# C64_PS.net
KiCad netlist of a schematic drawn in EAGLE
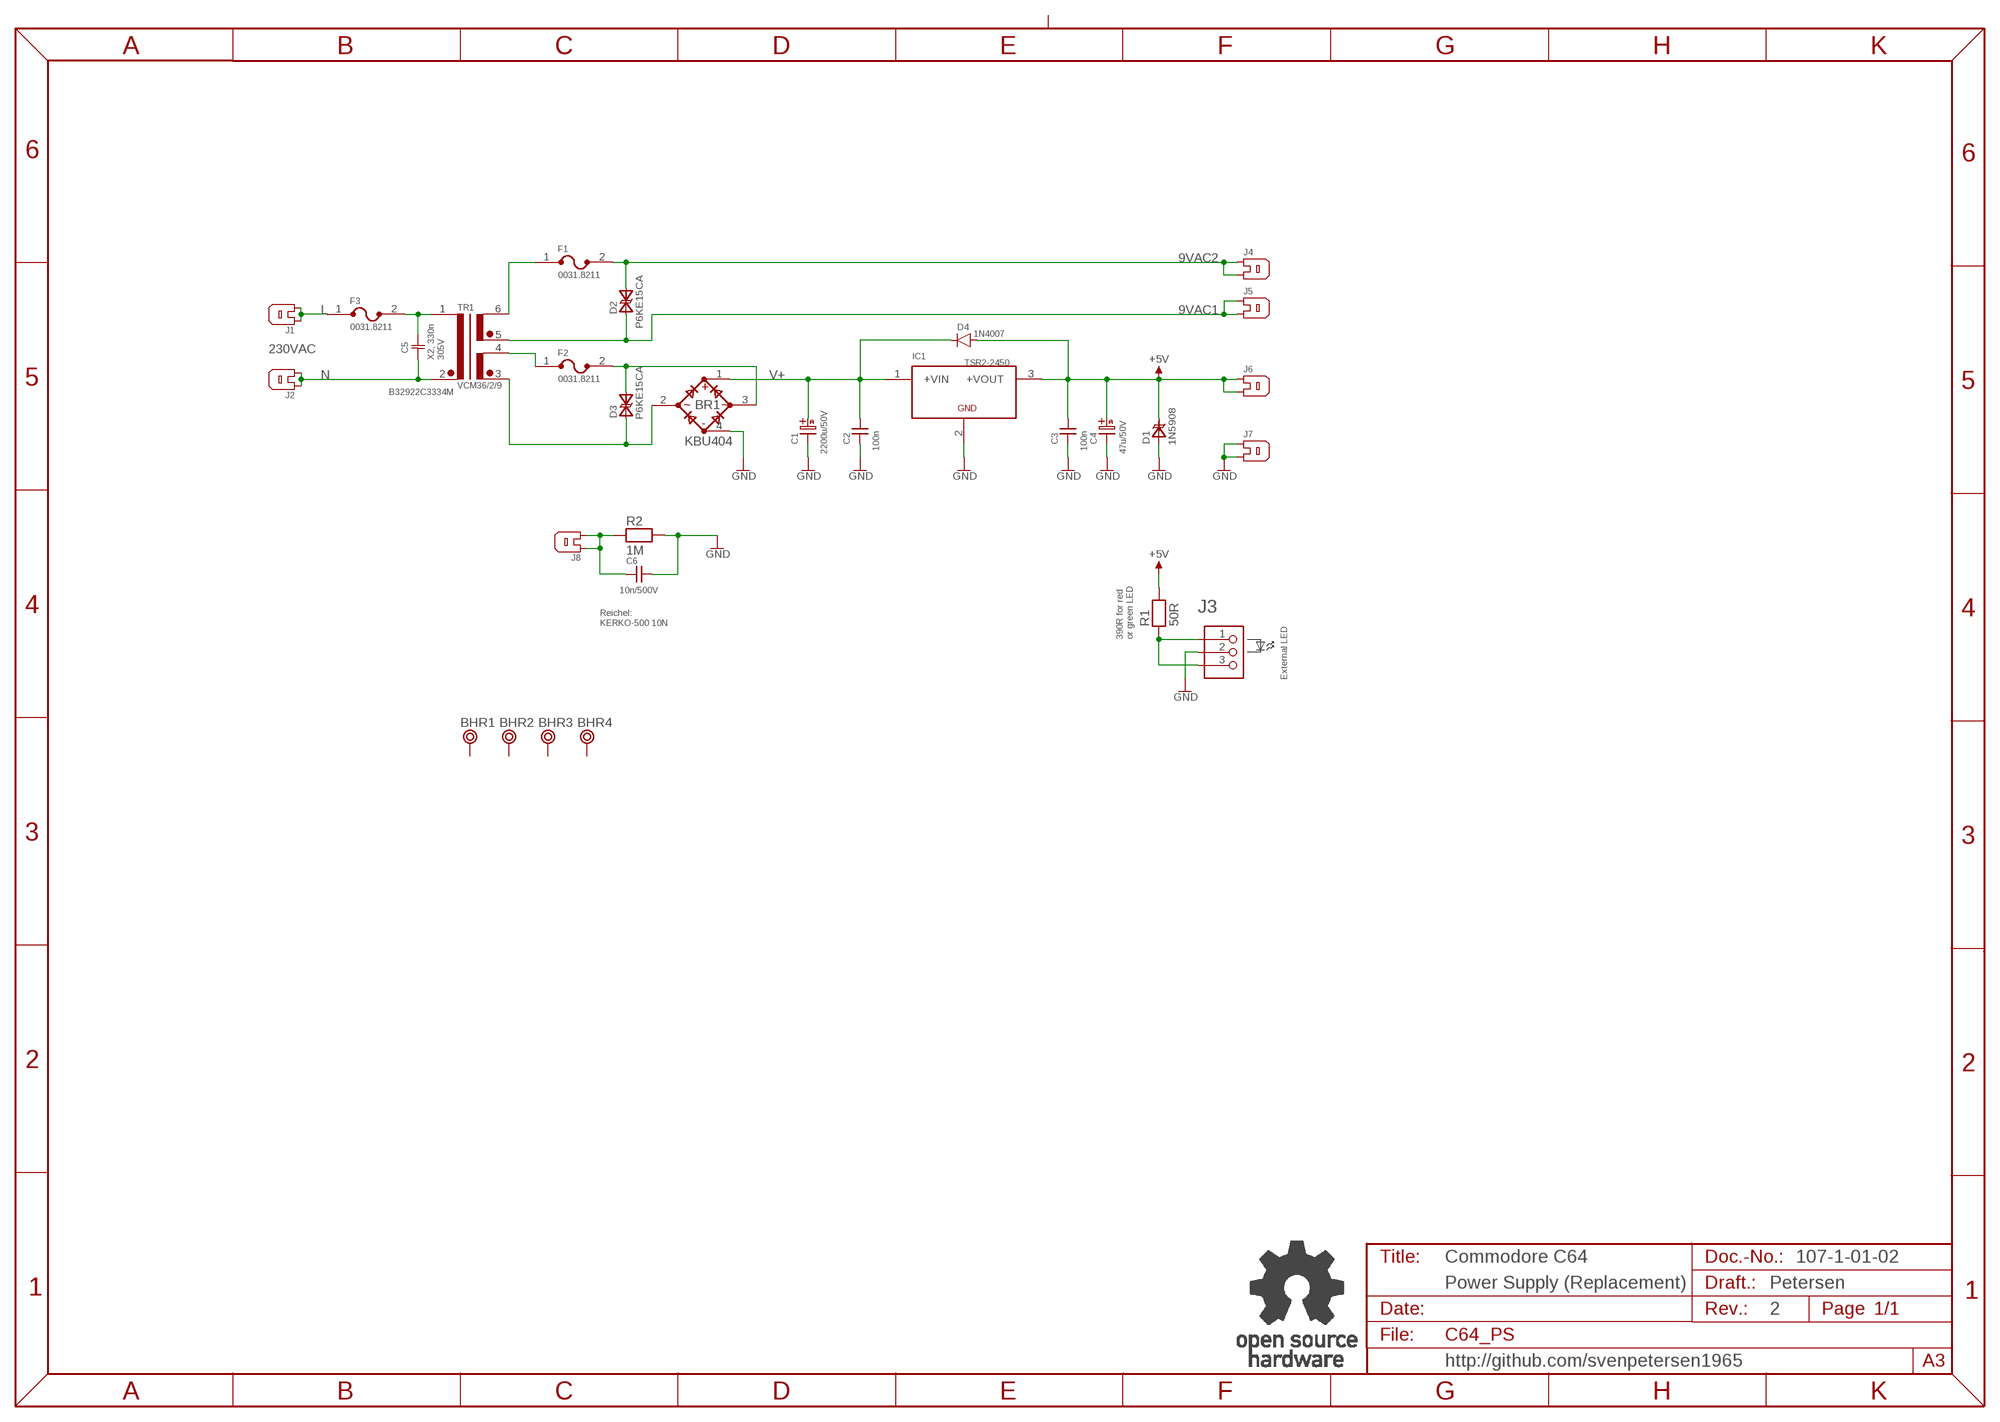
[diagram p0: schematic, sheet 1]

(export (version "E")
  (design (tool "Eeschema 10.0.6"))
  (components
    (comp (ref "BHR1")
      (value "BOHR3,3")
      (footprint "eagle-import:BOHR3,3")
      (libsource (lib "eagle-import") (part "BOHR3,3"))
    )
    (comp (ref "BHR2")
      (value "BOHR3,3")
      (footprint "eagle-import:BOHR3,3")
      (libsource (lib "eagle-import") (part "BOHR3,3"))
    )
    (comp (ref "BHR3")
      (value "BOHR3,3")
      (footprint "eagle-import:BOHR3,3")
      (libsource (lib "eagle-import") (part "BOHR3,3"))
    )
    (comp (ref "BHR4")
      (value "BOHR3,3")
      (footprint "eagle-import:BOHR3,3")
      (libsource (lib "eagle-import") (part "BOHR3,3"))
    )
    (comp (ref "BR1")
      (value "KBU404")
      (footprint "eagle-import:KBU")
      (libsource (lib "eagle-import") (part "KBU404"))
    )
    (comp (ref "C1")
      (value "2200u/50V")
      (footprint "eagle-import:C18_7,5")
      (libsource (lib "eagle-import") (part "C18/7,5"))
    )
    (comp (ref "C2")
      (value "100n")
      (footprint "eagle-import:C-5")
      (libsource (lib "eagle-import") (part "CAP02"))
    )
    (comp (ref "C3")
      (value "100n")
      (footprint "eagle-import:C-5")
      (libsource (lib "eagle-import") (part "CAP02"))
    )
    (comp (ref "C4")
      (value "47u/50V")
      (footprint "eagle-import:C07_2,5")
      (libsource (lib "eagle-import") (part "C07/2,5"))
    )
    (comp (ref "C5")
      (value "B32922C3334M")
      (footprint "eagle-import:C-18X8-RM15")
      (libsource (lib "eagle-import") (part "X2--RM15-18X8"))
    )
    (comp (ref "C6")
      (value "10n/500V")
      (footprint "eagle-import:C-5")
      (libsource (lib "eagle-import") (part "CAP02"))
    )
    (comp (ref "D1")
      (value "1N5908")
      (footprint "eagle-import:CB429")
      (libsource (lib "eagle-import") (part "1N5908"))
    )
    (comp (ref "D2")
      (value "P6KE15CA")
      (footprint "eagle-import:CB417")
      (libsource (lib "eagle-import") (part "P6KE15CA"))
    )
    (comp (ref "D3")
      (value "P6KE15CA")
      (footprint "eagle-import:CB417")
      (libsource (lib "eagle-import") (part "P6KE15CA"))
    )
    (comp (ref "D4")
      (value "1N4007")
      (footprint "eagle-import:DO-41")
      (libsource (lib "eagle-import") (part "1N4007"))
    )
    (comp (ref "F1")
      (value "0031.8211")
      (footprint "eagle-import:0031.8211")
      (libsource (lib "eagle-import") (part "0031.8211"))
    )
    (comp (ref "F2")
      (value "0031.8211")
      (footprint "eagle-import:0031.8211")
      (libsource (lib "eagle-import") (part "0031.8211"))
    )
    (comp (ref "F3")
      (value "0031.8211")
      (footprint "eagle-import:0031.8211")
      (libsource (lib "eagle-import") (part "0031.8211"))
    )
    (comp (ref "IC1")
      (value "TSR2-2450")
      (footprint "eagle-import:TSR2")
      (libsource (lib "eagle-import") (part "TSR2"))
    )
    (comp (ref "J1")
      (value "FLA6,3")
      (footprint "eagle-import:FLA6,3")
      (libsource (lib "eagle-import") (part "FLA6,3"))
    )
    (comp (ref "J2")
      (value "FLA6,3")
      (footprint "eagle-import:FLA6,3")
      (libsource (lib "eagle-import") (part "FLA6,3"))
    )
    (comp (ref "J3")
      (value "PINHD-1X3")
      (footprint "eagle-import:1X03")
      (libsource (lib "eagle-import") (part "PINHD-1X3"))
    )
    (comp (ref "J4")
      (value "FLA6,3")
      (footprint "eagle-import:FLA6,3")
      (libsource (lib "eagle-import") (part "FLA6,3"))
    )
    (comp (ref "J5")
      (value "FLA6,3")
      (footprint "eagle-import:FLA6,3")
      (libsource (lib "eagle-import") (part "FLA6,3"))
    )
    (comp (ref "J6")
      (value "FLA6,3")
      (footprint "eagle-import:FLA6,3")
      (libsource (lib "eagle-import") (part "FLA6,3"))
    )
    (comp (ref "J7")
      (value "FLA6,3")
      (footprint "eagle-import:FLA6,3")
      (libsource (lib "eagle-import") (part "FLA6,3"))
    )
    (comp (ref "J8")
      (value "FLA6,3")
      (footprint "eagle-import:FLA6,3")
      (libsource (lib "eagle-import") (part "FLA6,3"))
    )
    (comp (ref "R1")
      (value "50R")
      (footprint "eagle-import:R-10")
      (libsource (lib "eagle-import") (part "RES04"))
    )
    (comp (ref "R2")
      (value "1M")
      (footprint "eagle-import:R-10")
      (libsource (lib "eagle-import") (part "RES04"))
    )
    (comp (ref "TR1")
      (value "VCM36/2/9")
      (footprint "eagle-import:VCM36_2_9")
      (libsource (lib "eagle-import") (part "VCM36/2/9"))
    )
    (comp (ref "U$17")
      (value "OPEN_SOURCE_HW")
      (footprint "eagle-import:OPENHW")
      (libsource (lib "eagle-import") (part "OPEN_SOURCE_HW"))
    )
  )
  (nets
    (net (code "1") (name "+5V") (class "Default")
      (node (ref "C3") (pin "2") (pinfunction "2_2") (pintype "passive"))
      (node (ref "C4") (pin "A") (pinfunction "+_A") (pintype "passive"))
      (node (ref "D1") (pin "K") (pinfunction "K_K") (pintype "passive"))
      (node (ref "D4") (pin "A") (pinfunction "A_A") (pintype "passive"))
      (node (ref "IC1") (pin "3") (pinfunction "+VOUT_3") (pintype "output"))
      (node (ref "J6") (pin "1") (pinfunction "1_1") (pintype "passive"))
      (node (ref "J6") (pin "2") (pinfunction "2_2") (pintype "passive"))
      (node (ref "R1") (pin "2") (pinfunction "2_2") (pintype "passive"))
    )
    (net (code "2") (name "/9VAC1") (class "Default")
      (node (ref "D2") (pin "A") (pinfunction "A1_A") (pintype "passive"))
      (node (ref "J5") (pin "1") (pinfunction "1_1") (pintype "passive"))
      (node (ref "J5") (pin "2") (pinfunction "2_2") (pintype "passive"))
      (node (ref "TR1") (pin "5") (pinfunction "SEC12_5") (pintype "passive"))
    )
    (net (code "3") (name "/9VAC2") (class "Default")
      (node (ref "D2") (pin "K") (pinfunction "A2_K") (pintype "passive"))
      (node (ref "F1") (pin "2") (pinfunction "2_2") (pintype "passive"))
      (node (ref "J4") (pin "1") (pinfunction "1_1") (pintype "passive"))
      (node (ref "J4") (pin "2") (pinfunction "2_2") (pintype "passive"))
    )
    (net (code "4") (name "/L") (class "Default")
      (node (ref "F3") (pin "1") (pinfunction "1_1") (pintype "passive"))
      (node (ref "J1") (pin "1") (pinfunction "1_1") (pintype "passive"))
      (node (ref "J1") (pin "2") (pinfunction "2_2") (pintype "passive"))
    )
    (net (code "5") (name "/N") (class "Default")
      (node (ref "C5") (pin "1") (pinfunction "1_1") (pintype "passive"))
      (node (ref "J2") (pin "1") (pinfunction "1_1") (pintype "passive"))
      (node (ref "J2") (pin "2") (pinfunction "2_2") (pintype "passive"))
      (node (ref "TR1") (pin "2") (pinfunction "PRI2_2") (pintype "passive"))
    )
    (net (code "6") (name "/V+") (class "Default")
      (node (ref "BR1") (pin "1") (pinfunction "+_1") (pintype "passive"))
      (node (ref "C1") (pin "+") (pinfunction "+_+") (pintype "passive"))
      (node (ref "C2") (pin "2") (pinfunction "2_2") (pintype "passive"))
      (node (ref "D4") (pin "K") (pinfunction "K_K") (pintype "passive"))
      (node (ref "IC1") (pin "1") (pinfunction "+VIN_1") (pintype "input"))
    )
    (net (code "7") (name "GND") (class "Default")
      (node (ref "BR1") (pin "4") (pinfunction "-_4") (pintype "passive"))
      (node (ref "C1") (pin "-") (pinfunction "-_-") (pintype "passive"))
      (node (ref "C2") (pin "1") (pinfunction "1_1") (pintype "passive"))
      (node (ref "C3") (pin "1") (pinfunction "1_1") (pintype "passive"))
      (node (ref "C4") (pin "K") (pinfunction "-_K") (pintype "passive"))
      (node (ref "C6") (pin "2") (pinfunction "2_2") (pintype "passive"))
      (node (ref "D1") (pin "A") (pinfunction "A_A") (pintype "passive"))
      (node (ref "IC1") (pin "2") (pinfunction "GND_2") (pintype "passive"))
      (node (ref "J3") (pin "2") (pinfunction "2_2") (pintype "passive"))
      (node (ref "J7") (pin "1") (pinfunction "1_1") (pintype "passive"))
      (node (ref "J7") (pin "2") (pinfunction "2_2") (pintype "passive"))
      (node (ref "R2") (pin "2") (pinfunction "2_2") (pintype "passive"))
    )
    (net (code "8") (name "Net-(BR1-AC1)") (class "Default")
      (node (ref "BR1") (pin "2") (pinfunction "AC1_2") (pintype "passive"))
      (node (ref "D3") (pin "A") (pinfunction "A1_A") (pintype "passive"))
      (node (ref "TR1") (pin "3") (pinfunction "SEC22_3") (pintype "passive"))
    )
    (net (code "9") (name "Net-(BR1-AC2)") (class "Default")
      (node (ref "BR1") (pin "3") (pinfunction "AC2_3") (pintype "passive"))
      (node (ref "D3") (pin "K") (pinfunction "A2_K") (pintype "passive"))
      (node (ref "F2") (pin "2") (pinfunction "2_2") (pintype "passive"))
    )
    (net (code "10") (name "Net-(C6-Pad1)") (class "Default")
      (node (ref "C6") (pin "1") (pinfunction "1_1") (pintype "passive"))
      (node (ref "J8") (pin "1") (pinfunction "1_1") (pintype "passive"))
      (node (ref "J8") (pin "2") (pinfunction "2_2") (pintype "passive"))
      (node (ref "R2") (pin "1") (pinfunction "1_1") (pintype "passive"))
    )
    (net (code "11") (name "Net-(J3-Pad1)") (class "Default")
      (node (ref "J3") (pin "1") (pinfunction "1_1") (pintype "passive"))
      (node (ref "J3") (pin "3") (pinfunction "3_3") (pintype "passive"))
      (node (ref "R1") (pin "1") (pinfunction "1_1") (pintype "passive"))
    )
    (net (code "12") (name "Net-(TR1-PRI1)") (class "Default")
      (node (ref "C5") (pin "2") (pinfunction "2_2") (pintype "passive"))
      (node (ref "F3") (pin "2") (pinfunction "2_2") (pintype "passive"))
      (node (ref "TR1") (pin "1") (pinfunction "PRI1_1") (pintype "passive"))
    )
    (net (code "13") (name "Net-(TR1-SEC11)") (class "Default")
      (node (ref "F1") (pin "1") (pinfunction "1_1") (pintype "passive"))
      (node (ref "TR1") (pin "6") (pinfunction "SEC11_6") (pintype "passive"))
    )
    (net (code "14") (name "Net-(TR1-SEC21)") (class "Default")
      (node (ref "F2") (pin "1") (pinfunction "1_1") (pintype "passive"))
      (node (ref "TR1") (pin "4") (pinfunction "SEC21_4") (pintype "passive"))
    )
    (net (code "15") (name "unconnected-(BHR1-PadP$1)") (class "Default")
      (node (ref "BHR1") (pin "P$1") (pinfunction "P$1_P$1") (pintype "passive"))
    )
    (net (code "16") (name "unconnected-(BHR2-PadP$1)") (class "Default")
      (node (ref "BHR2") (pin "P$1") (pinfunction "P$1_P$1") (pintype "passive"))
    )
    (net (code "17") (name "unconnected-(BHR3-PadP$1)") (class "Default")
      (node (ref "BHR3") (pin "P$1") (pinfunction "P$1_P$1") (pintype "passive"))
    )
    (net (code "18") (name "unconnected-(BHR4-PadP$1)") (class "Default")
      (node (ref "BHR4") (pin "P$1") (pinfunction "P$1_P$1") (pintype "passive"))
    )
  )
)
